# Signal_Pow_Reg_SCH.net
KiCad netlist of a schematic drawn in Altium Designer
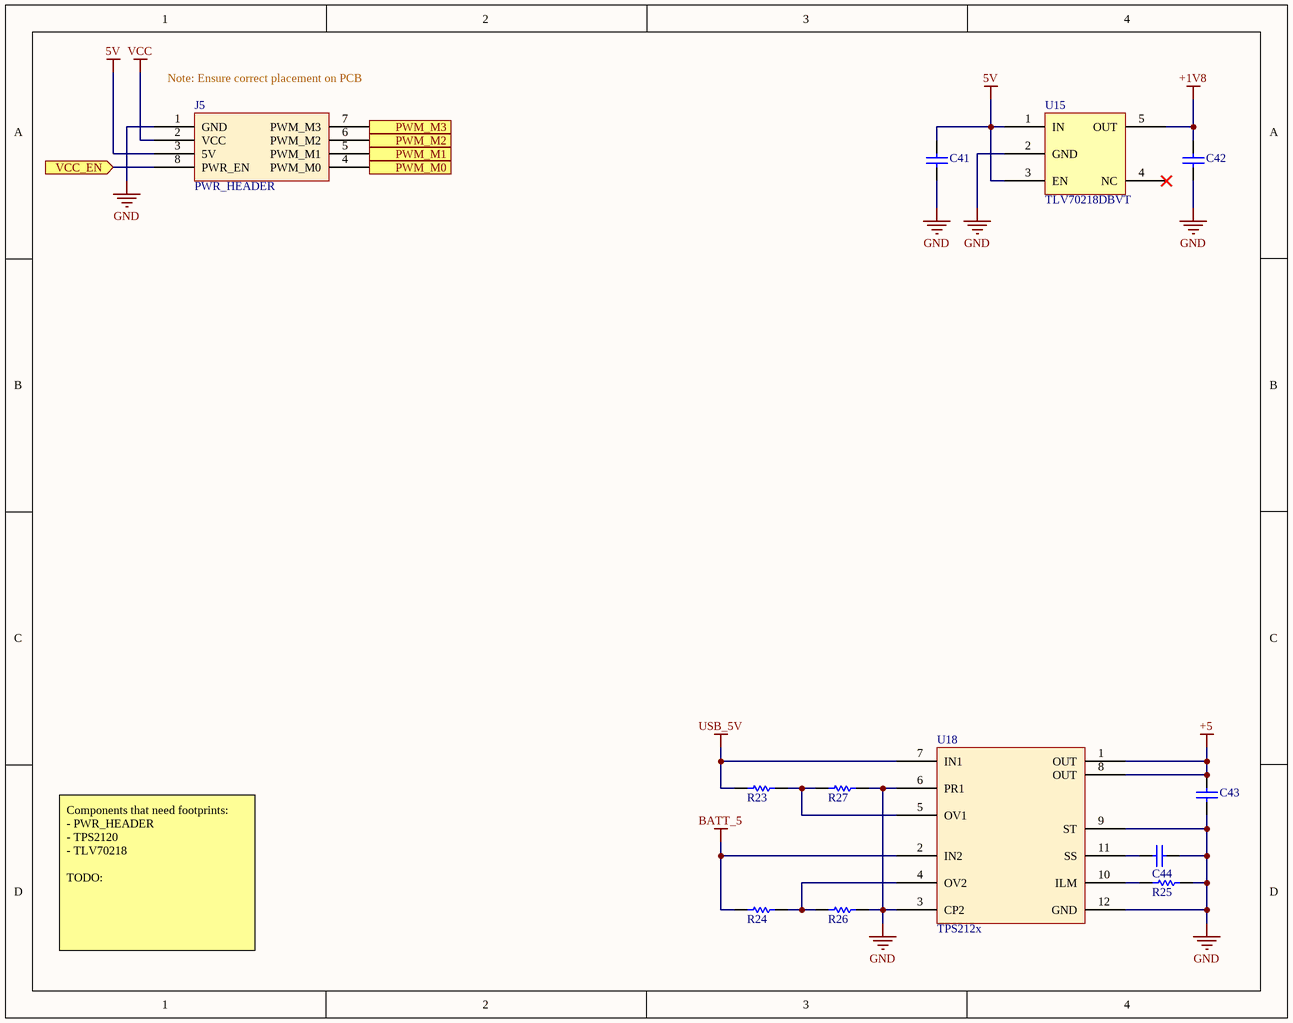
[diagram p0: Signal_Pow_Reg_SCH.SchDoc]

(export (version "E")
  (design (tool "Eeschema 10.0.6"))
  (components
    (comp (ref "C41")
      (value "08055C104KAJ2A")
      (footprint "CAPC2013X140X50NL20T25")
      (fields (field (name "MANUFACTURER") "AVX Interconnect / Elco"))
      (libsource (lib "Altium Content Vault") (part "CAP"))
    )
    (comp (ref "C42")
      (value "08055C104KAJ2A")
      (footprint "CAPC2013X140X50NL20T25")
      (fields (field (name "MANUFACTURER") "AVX Interconnect / Elco"))
      (libsource (lib "Altium Content Vault") (part "CAP"))
    )
    (comp (ref "C43")
      (value "08055C104KAJ2A")
      (footprint "CAPC2013X140X50NL20T25")
      (fields (field (name "MANUFACTURER") "AVX Interconnect / Elco"))
      (libsource (lib "Altium Content Vault") (part "CAP"))
    )
    (comp (ref "C44")
      (value "08055C104KAJ2A")
      (footprint "CAPC2013X140X50NL20T25")
      (fields (field (name "MANUFACTURER") "AVX Interconnect / Elco"))
      (libsource (lib "Altium Content Vault") (part "CAP"))
    )
    (comp (ref "J5") (value "PWR_HEADER") (libsource (lib "Copter") (part "PWR_HEADER")))
    (comp (ref "R23")
      (value "ERJ-6ENF1503V")
      (footprint "RESC2013X70X40LL20T20")
      (description "RES SMD 150K OHM 1% 1/8W 0805")
      (fields (field (name "MANUFACTURER") "Panasonic"))
      (libsource (lib "Altium Content Vault") (part "RES"))
    )
    (comp (ref "R24")
      (value "ERJ-6ENF1503V")
      (footprint "RESC2013X70X40LL20T20")
      (description "RES SMD 150K OHM 1% 1/8W 0805")
      (fields (field (name "MANUFACTURER") "Panasonic"))
      (libsource (lib "Altium Content Vault") (part "RES"))
    )
    (comp (ref "R25")
      (value "ERJ-6ENF1503V")
      (footprint "RESC2013X70X40LL20T20")
      (description "RES SMD 150K OHM 1% 1/8W 0805")
      (fields (field (name "MANUFACTURER") "Panasonic"))
      (libsource (lib "Altium Content Vault") (part "RES"))
    )
    (comp (ref "R26")
      (value "ERJ-6ENF1503V")
      (footprint "RESC2013X70X40LL20T20")
      (description "RES SMD 150K OHM 1% 1/8W 0805")
      (fields (field (name "MANUFACTURER") "Panasonic"))
      (libsource (lib "Altium Content Vault") (part "RES"))
    )
    (comp (ref "R27")
      (value "ERJ-6ENF1503V")
      (footprint "RESC2013X70X40LL20T20")
      (description "RES SMD 150K OHM 1% 1/8W 0805")
      (fields (field (name "MANUFACTURER") "Panasonic"))
      (libsource (lib "Altium Content Vault") (part "RES"))
    )
    (comp (ref "U15") (value "TLV70218DBVT") (libsource (lib "Copter") (part "TLV702")))
    (comp (ref "U18")
      (value "TPS212x")
      (description "PWR MGMT BATTERY MGMT")
      (libsource (lib "Copter") (part "TPS212x"))
    )
  )
  (nets
    (net (code "1") (name "+1V8") (class "Default")
      (node (ref "C42") (pin "2") (pinfunction "2_2") (pintype "passive"))
      (node (ref "U15") (pin "5") (pinfunction "OUT_5") (pintype "passive"))
    )
    (net (code "2") (name "+5") (class "Default")
      (node (ref "C43") (pin "2") (pinfunction "2_2") (pintype "passive"))
      (node (ref "U18") (pin "1") (pinfunction "OUT_1") (pintype "passive"))
      (node (ref "U18") (pin "8") (pinfunction "OUT_8") (pintype "passive"))
    )
    (net (code "3") (name "/PWM_M0") (class "Default")
      (node (ref "J5") (pin "4") (pinfunction "PWM_M0_4") (pintype "passive"))
    )
    (net (code "4") (name "/PWM_M1") (class "Default")
      (node (ref "J5") (pin "5") (pinfunction "PWM_M1_5") (pintype "passive"))
    )
    (net (code "5") (name "/PWM_M2") (class "Default")
      (node (ref "J5") (pin "6") (pinfunction "PWM_M2_6") (pintype "passive"))
    )
    (net (code "6") (name "/PWM_M3") (class "Default")
      (node (ref "J5") (pin "7") (pinfunction "PWM_M3_7") (pintype "passive"))
    )
    (net (code "7") (name "/VCC_EN") (class "Default")
      (node (ref "J5") (pin "8") (pinfunction "PWR_EN_8") (pintype "passive"))
    )
    (net (code "8") (name "5V") (class "Default")
      (node (ref "C41") (pin "2") (pinfunction "2_2") (pintype "passive"))
      (node (ref "J5") (pin "3") (pinfunction "5V_3") (pintype "passive"))
      (node (ref "U15") (pin "1") (pinfunction "IN_1") (pintype "passive"))
      (node (ref "U15") (pin "3") (pinfunction "EN_3") (pintype "passive"))
    )
    (net (code "9") (name "BATT_5") (class "Default")
      (node (ref "R24") (pin "2") (pinfunction "2_2") (pintype "passive"))
      (node (ref "U18") (pin "2") (pinfunction "IN2_2") (pintype "passive"))
    )
    (net (code "10") (name "GND") (class "Default")
      (node (ref "C41") (pin "1") (pinfunction "1_1") (pintype "passive"))
      (node (ref "C42") (pin "1") (pinfunction "1_1") (pintype "passive"))
      (node (ref "C43") (pin "1") (pinfunction "1_1") (pintype "passive"))
      (node (ref "C44") (pin "2") (pinfunction "2_2") (pintype "passive"))
      (node (ref "J5") (pin "1") (pinfunction "GND_1") (pintype "passive"))
      (node (ref "R25") (pin "2") (pinfunction "2_2") (pintype "passive"))
      (node (ref "R26") (pin "2") (pinfunction "2_2") (pintype "passive"))
      (node (ref "R27") (pin "2") (pinfunction "2_2") (pintype "passive"))
      (node (ref "U15") (pin "2") (pinfunction "GND_2") (pintype "passive"))
      (node (ref "U18") (pin "12") (pinfunction "GND_12") (pintype "passive"))
      (node (ref "U18") (pin "3") (pinfunction "CP2_3") (pintype "passive"))
      (node (ref "U18") (pin "6") (pinfunction "PR1_6") (pintype "passive"))
      (node (ref "U18") (pin "9") (pinfunction "ST_9") (pintype "passive"))
    )
    (net (code "11") (name "Net-(U18-ILM)") (class "Default")
      (node (ref "R25") (pin "1") (pinfunction "1_1") (pintype "passive"))
      (node (ref "U18") (pin "10") (pinfunction "ILM_10") (pintype "passive"))
    )
    (net (code "12") (name "Net-(U18-OV1)") (class "Default")
      (node (ref "R23") (pin "1") (pinfunction "1_1") (pintype "passive"))
      (node (ref "R27") (pin "1") (pinfunction "1_1") (pintype "passive"))
      (node (ref "U18") (pin "5") (pinfunction "OV1_5") (pintype "passive"))
    )
    (net (code "13") (name "Net-(U18-OV2)") (class "Default")
      (node (ref "R24") (pin "1") (pinfunction "1_1") (pintype "passive"))
      (node (ref "R26") (pin "1") (pinfunction "1_1") (pintype "passive"))
      (node (ref "U18") (pin "4") (pinfunction "OV2_4") (pintype "passive"))
    )
    (net (code "14") (name "Net-(U18-SS)") (class "Default")
      (node (ref "C44") (pin "1") (pinfunction "1_1") (pintype "passive"))
      (node (ref "U18") (pin "11") (pinfunction "SS_11") (pintype "passive"))
    )
    (net (code "15") (name "USB_5V") (class "Default")
      (node (ref "R23") (pin "2") (pinfunction "2_2") (pintype "passive"))
      (node (ref "U18") (pin "7") (pinfunction "IN1_7") (pintype "passive"))
    )
    (net (code "16") (name "VCC") (class "Default")
      (node (ref "J5") (pin "2") (pinfunction "VCC_2") (pintype "passive"))
    )
    (net (code "17") (name "unconnected-(U15-NC-Pad4)") (class "Default")
      (node (ref "U15") (pin "4") (pinfunction "NC_4") (pintype "passive+no_connect"))
    )
  )
)
